# ui.net
KiCad netlist of a schematic drawn in Altium Designer
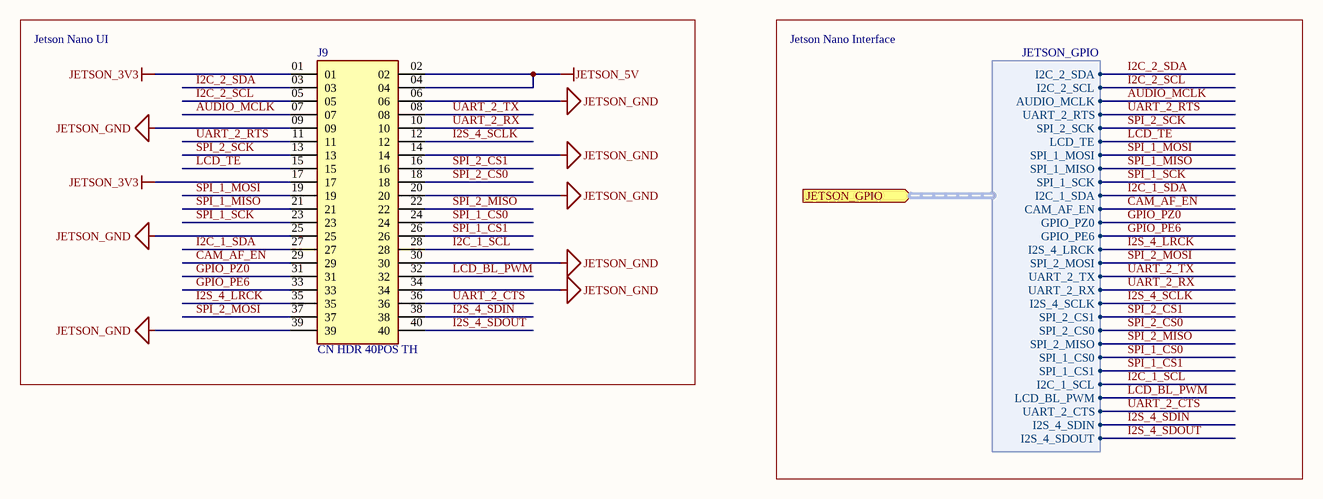
[diagram p0: ui.SchDoc]

(export (version "E")
  (design (tool "Eeschema 10.0.6"))
  (components
    (comp (ref "J9")
      (value "CN HDR 40POS TH")
      (footprint "SAMTEC_SSQ-120-22-G-D")
      (description "SSQ - Samtec 2.54mm Square Tail Dual Row Socket Strip 8.5mm Profile")
      (fields (field (name "MF") "Samtec") (field (name "MP") "SSQ-120-22-G-D"))
      (libsource (lib "AltiumLibraries") (part "CN HDR 40POS TH"))
    )
  )
  (nets
    (net (code "2") (name "/AUDIO_MCLK") (class "Default")
      (node (ref "J9") (pin "07") (pinfunction "07_07") (pintype "passive"))
    )
    (net (code "3") (name "/CAM_AF_EN") (class "Default")
      (node (ref "J9") (pin "29") (pinfunction "29_29") (pintype "passive"))
    )
    (net (code "4") (name "/GPIO_PE6") (class "Default")
      (node (ref "J9") (pin "33") (pinfunction "33_33") (pintype "passive"))
    )
    (net (code "5") (name "/GPIO_PZ0") (class "Default")
      (node (ref "J9") (pin "31") (pinfunction "31_31") (pintype "passive"))
    )
    (net (code "6") (name "/I2C_1_SCL") (class "Default")
      (node (ref "J9") (pin "28") (pinfunction "28_28") (pintype "passive"))
    )
    (net (code "7") (name "/I2C_1_SDA") (class "Default")
      (node (ref "J9") (pin "27") (pinfunction "27_27") (pintype "passive"))
    )
    (net (code "8") (name "/I2C_2_SCL") (class "Default")
      (node (ref "J9") (pin "05") (pinfunction "05_05") (pintype "passive"))
    )
    (net (code "9") (name "/I2C_2_SDA") (class "Default")
      (node (ref "J9") (pin "03") (pinfunction "03_03") (pintype "passive"))
    )
    (net (code "10") (name "/I2S_4_LRCK") (class "Default")
      (node (ref "J9") (pin "35") (pinfunction "35_35") (pintype "passive"))
    )
    (net (code "11") (name "/I2S_4_SCLK") (class "Default")
      (node (ref "J9") (pin "12") (pinfunction "12_12") (pintype "passive"))
    )
    (net (code "12") (name "/I2S_4_SDIN") (class "Default")
      (node (ref "J9") (pin "38") (pinfunction "38_38") (pintype "passive"))
    )
    (net (code "13") (name "/I2S_4_SDOUT") (class "Default")
      (node (ref "J9") (pin "40") (pinfunction "40_40") (pintype "passive"))
    )
    (net (code "14") (name "/LCD_BL_PWM") (class "Default")
      (node (ref "J9") (pin "32") (pinfunction "32_32") (pintype "passive"))
    )
    (net (code "15") (name "/LCD_TE") (class "Default")
      (node (ref "J9") (pin "15") (pinfunction "15_15") (pintype "passive"))
    )
    (net (code "16") (name "/SPI_1_CS0") (class "Default")
      (node (ref "J9") (pin "24") (pinfunction "24_24") (pintype "passive"))
    )
    (net (code "17") (name "/SPI_1_CS1") (class "Default")
      (node (ref "J9") (pin "26") (pinfunction "26_26") (pintype "passive"))
    )
    (net (code "18") (name "/SPI_1_MISO") (class "Default")
      (node (ref "J9") (pin "21") (pinfunction "21_21") (pintype "passive"))
    )
    (net (code "19") (name "/SPI_1_MOSI") (class "Default")
      (node (ref "J9") (pin "19") (pinfunction "19_19") (pintype "passive"))
    )
    (net (code "20") (name "/SPI_1_SCK") (class "Default")
      (node (ref "J9") (pin "23") (pinfunction "23_23") (pintype "passive"))
    )
    (net (code "21") (name "/SPI_2_CS0") (class "Default")
      (node (ref "J9") (pin "18") (pinfunction "18_18") (pintype "passive"))
    )
    (net (code "22") (name "/SPI_2_CS1") (class "Default")
      (node (ref "J9") (pin "16") (pinfunction "16_16") (pintype "passive"))
    )
    (net (code "23") (name "/SPI_2_MISO") (class "Default")
      (node (ref "J9") (pin "22") (pinfunction "22_22") (pintype "passive"))
    )
    (net (code "24") (name "/SPI_2_MOSI") (class "Default")
      (node (ref "J9") (pin "37") (pinfunction "37_37") (pintype "passive"))
    )
    (net (code "25") (name "/SPI_2_SCK") (class "Default")
      (node (ref "J9") (pin "13") (pinfunction "13_13") (pintype "passive"))
    )
    (net (code "26") (name "/UART_2_CTS") (class "Default")
      (node (ref "J9") (pin "36") (pinfunction "36_36") (pintype "passive"))
    )
    (net (code "27") (name "/UART_2_RTS") (class "Default")
      (node (ref "J9") (pin "11") (pinfunction "11_11") (pintype "passive"))
    )
    (net (code "28") (name "/UART_2_RX") (class "Default")
      (node (ref "J9") (pin "10") (pinfunction "10_10") (pintype "passive"))
    )
    (net (code "29") (name "/UART_2_TX") (class "Default")
      (node (ref "J9") (pin "08") (pinfunction "08_08") (pintype "passive"))
    )
    (net (code "31") (name "JETSON_3V3") (class "Default")
      (node (ref "J9") (pin "01") (pinfunction "01_01") (pintype "passive"))
      (node (ref "J9") (pin "17") (pinfunction "17_17") (pintype "passive"))
    )
    (net (code "32") (name "JETSON_5V") (class "Default")
      (node (ref "J9") (pin "02") (pinfunction "02_02") (pintype "passive"))
      (node (ref "J9") (pin "04") (pinfunction "04_04") (pintype "passive"))
    )
    (net (code "33") (name "JETSON_GND") (class "Default")
      (node (ref "J9") (pin "06") (pinfunction "06_06") (pintype "passive"))
      (node (ref "J9") (pin "09") (pinfunction "09_09") (pintype "passive"))
      (node (ref "J9") (pin "14") (pinfunction "14_14") (pintype "passive"))
      (node (ref "J9") (pin "20") (pinfunction "20_20") (pintype "passive"))
      (node (ref "J9") (pin "25") (pinfunction "25_25") (pintype "passive"))
      (node (ref "J9") (pin "30") (pinfunction "30_30") (pintype "passive"))
      (node (ref "J9") (pin "34") (pinfunction "34_34") (pintype "passive"))
      (node (ref "J9") (pin "39") (pinfunction "39_39") (pintype "passive"))
    )
  )
)
